# AFE_Power.net
KiCad netlist of a schematic drawn in Altium Designer
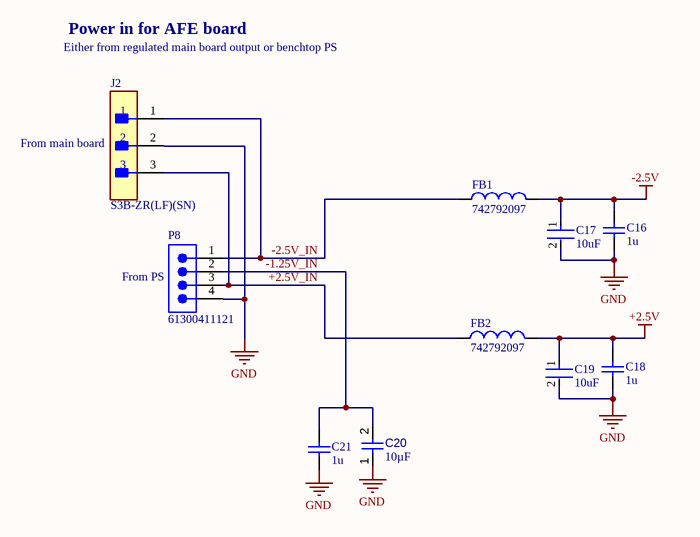
[diagram p0: AFE_Power.SchDoc]

(export (version "E")
  (design (tool "Eeschema 10.0.6"))
  (components
    (comp (ref "C16")
      (value "1u")
      (footprint "WCAP-CSGP_0402_L1W0.5H0.5")
      (description "CAP CER 10000PF 50V X7R 0402")
      (fields (field (name "TOLERANCE") "10%"))
      (libsource (lib "Altium Content Vault") (part "Capacitor_Non-Polarized"))
    )
    (comp (ref "C17")
      (value "10uF")
      (footprint "FP-GRM188-0_1-e0_2_0_55-IPC_A")
      (description "Chip Multilayer Ceramic Capacitors for General Purpose, 0603, 10uF, X5R, 15%, 20%, 6.3V")
      (fields (field (name "VOLTAGE") "6.3V") (field (name "TOLERANCE") "20%"))
      (libsource (lib "Altium Content Vault") (part "02cd4be3c70576c341d710602a673aa"))
    )
    (comp (ref "C18")
      (value "1u")
      (footprint "WCAP-CSGP_0402_L1W0.5H0.5")
      (description "CAP CER 10000PF 50V X7R 0402")
      (fields (field (name "TOLERANCE") "10%"))
      (libsource (lib "Altium Content Vault") (part "Capacitor_Non-Polarized"))
    )
    (comp (ref "C19")
      (value "10uF")
      (footprint "FP-GRM188-0_1-e0_2_0_55-IPC_A")
      (description "Chip Multilayer Ceramic Capacitors for General Purpose, 0603, 10uF, X5R, 15%, 20%, 6.3V")
      (fields (field (name "VOLTAGE") "6.3V") (field (name "TOLERANCE") "20%"))
      (libsource (lib "Altium Content Vault") (part "02cd4be3c70576c341d710602a673aa"))
    )
    (comp (ref "C20")
      (value "10µF")
      (footprint "CAPC0603(1608)100_L")
      (description "Chip Capacitor, 10µF +/-20%, 10V, 0603, Thickness 1 mm")
      (fields (field (name "TOLERANCE") "10%") (field (name "Comment") "Capacitor 10µF +/-20% 10V 0603"))
      (libsource (lib "Christian Fenger") (part "CAP-NP-2"))
    )
    (comp (ref "C21")
      (value "1u")
      (footprint "WCAP-CSGP_0402_L1W0.5H0.5")
      (description "CAP CER 10000PF 50V X7R 0402")
      (fields (field (name "TOLERANCE") "10%"))
      (libsource (lib "Altium Content Vault") (part "Capacitor_Non-Polarized"))
    )
    (comp (ref "FB1")
      (value "742792097")
      (footprint "WE-CBF_0805_L2W1.2H0.9_HC")
      (fields (field (name "TOLERANCE") "25%"))
      (libsource (lib "Altium Content Vault") (part "Ferrite"))
    )
    (comp (ref "FB2")
      (value "742792097")
      (footprint "WE-CBF_0805_L2W1.2H0.9_HC")
      (fields (field (name "TOLERANCE") "25%"))
      (libsource (lib "Altium Content Vault") (part "Ferrite"))
    )
    (comp (ref "J2")
      (value "S3B-ZR(LF)(SN)")
      (footprint "FP-S3B-ZR_LF_SN-MFG")
      (description "CONN HEADER R/A 3POS 1.5MM")
      (libsource (lib "Altium Content Vault") (part "0d3f023dd272f625e17a2be33dea85f"))
    )
    (comp (ref "P8")
      (value "61300411121")
      (footprint "61300411121")
      (libsource (lib "Altium Content Vault") (part "Header_Male_1R_04P"))
    )
  )
  (nets
    (net (code "1") (name "+2.5V") (class "Default")
      (node (ref "C18") (pin "2") (pinfunction "2_2") (pintype "passive"))
      (node (ref "C19") (pin "1") (pinfunction "1_1") (pintype "passive"))
      (node (ref "FB2") (pin "2") (pinfunction "2_2") (pintype "passive"))
    )
    (net (code "2") (name "-2.5V") (class "Default")
      (node (ref "C16") (pin "2") (pinfunction "2_2") (pintype "passive"))
      (node (ref "C17") (pin "1") (pinfunction "1_1") (pintype "passive"))
      (node (ref "FB1") (pin "2") (pinfunction "2_2") (pintype "passive"))
    )
    (net (code "3") (name "/+2.5V_IN") (class "Default")
      (node (ref "FB2") (pin "1") (pinfunction "1_1") (pintype "passive"))
      (node (ref "J2") (pin "3") (pinfunction "3_3") (pintype "passive"))
      (node (ref "P8") (pin "3") (pinfunction "3_3") (pintype "passive"))
    )
    (net (code "4") (name "/-1.25V_IN") (class "Default")
      (node (ref "C20") (pin "2") (pinfunction "2_2") (pintype "passive"))
      (node (ref "C21") (pin "2") (pinfunction "2_2") (pintype "passive"))
      (node (ref "P8") (pin "2") (pinfunction "2_2") (pintype "passive"))
    )
    (net (code "5") (name "/-2.5V_IN") (class "Default")
      (node (ref "FB1") (pin "1") (pinfunction "1_1") (pintype "passive"))
      (node (ref "J2") (pin "1") (pinfunction "1_1") (pintype "passive"))
      (node (ref "P8") (pin "1") (pinfunction "1_1") (pintype "passive"))
    )
    (net (code "6") (name "GND") (class "Default")
      (node (ref "C16") (pin "1") (pinfunction "1_1") (pintype "passive"))
      (node (ref "C17") (pin "2") (pinfunction "2_2") (pintype "passive"))
      (node (ref "C18") (pin "1") (pinfunction "1_1") (pintype "passive"))
      (node (ref "C19") (pin "2") (pinfunction "2_2") (pintype "passive"))
      (node (ref "C20") (pin "1") (pinfunction "1_1") (pintype "passive"))
      (node (ref "C21") (pin "1") (pinfunction "1_1") (pintype "passive"))
      (node (ref "J2") (pin "2") (pinfunction "2_2") (pintype "passive"))
      (node (ref "P8") (pin "4") (pinfunction "4_4") (pintype "passive"))
    )
  )
)
